# ProPrj_SunLight_2026-07-16.net
KiCad netlist of a schematic drawn in EasyEDA Pro
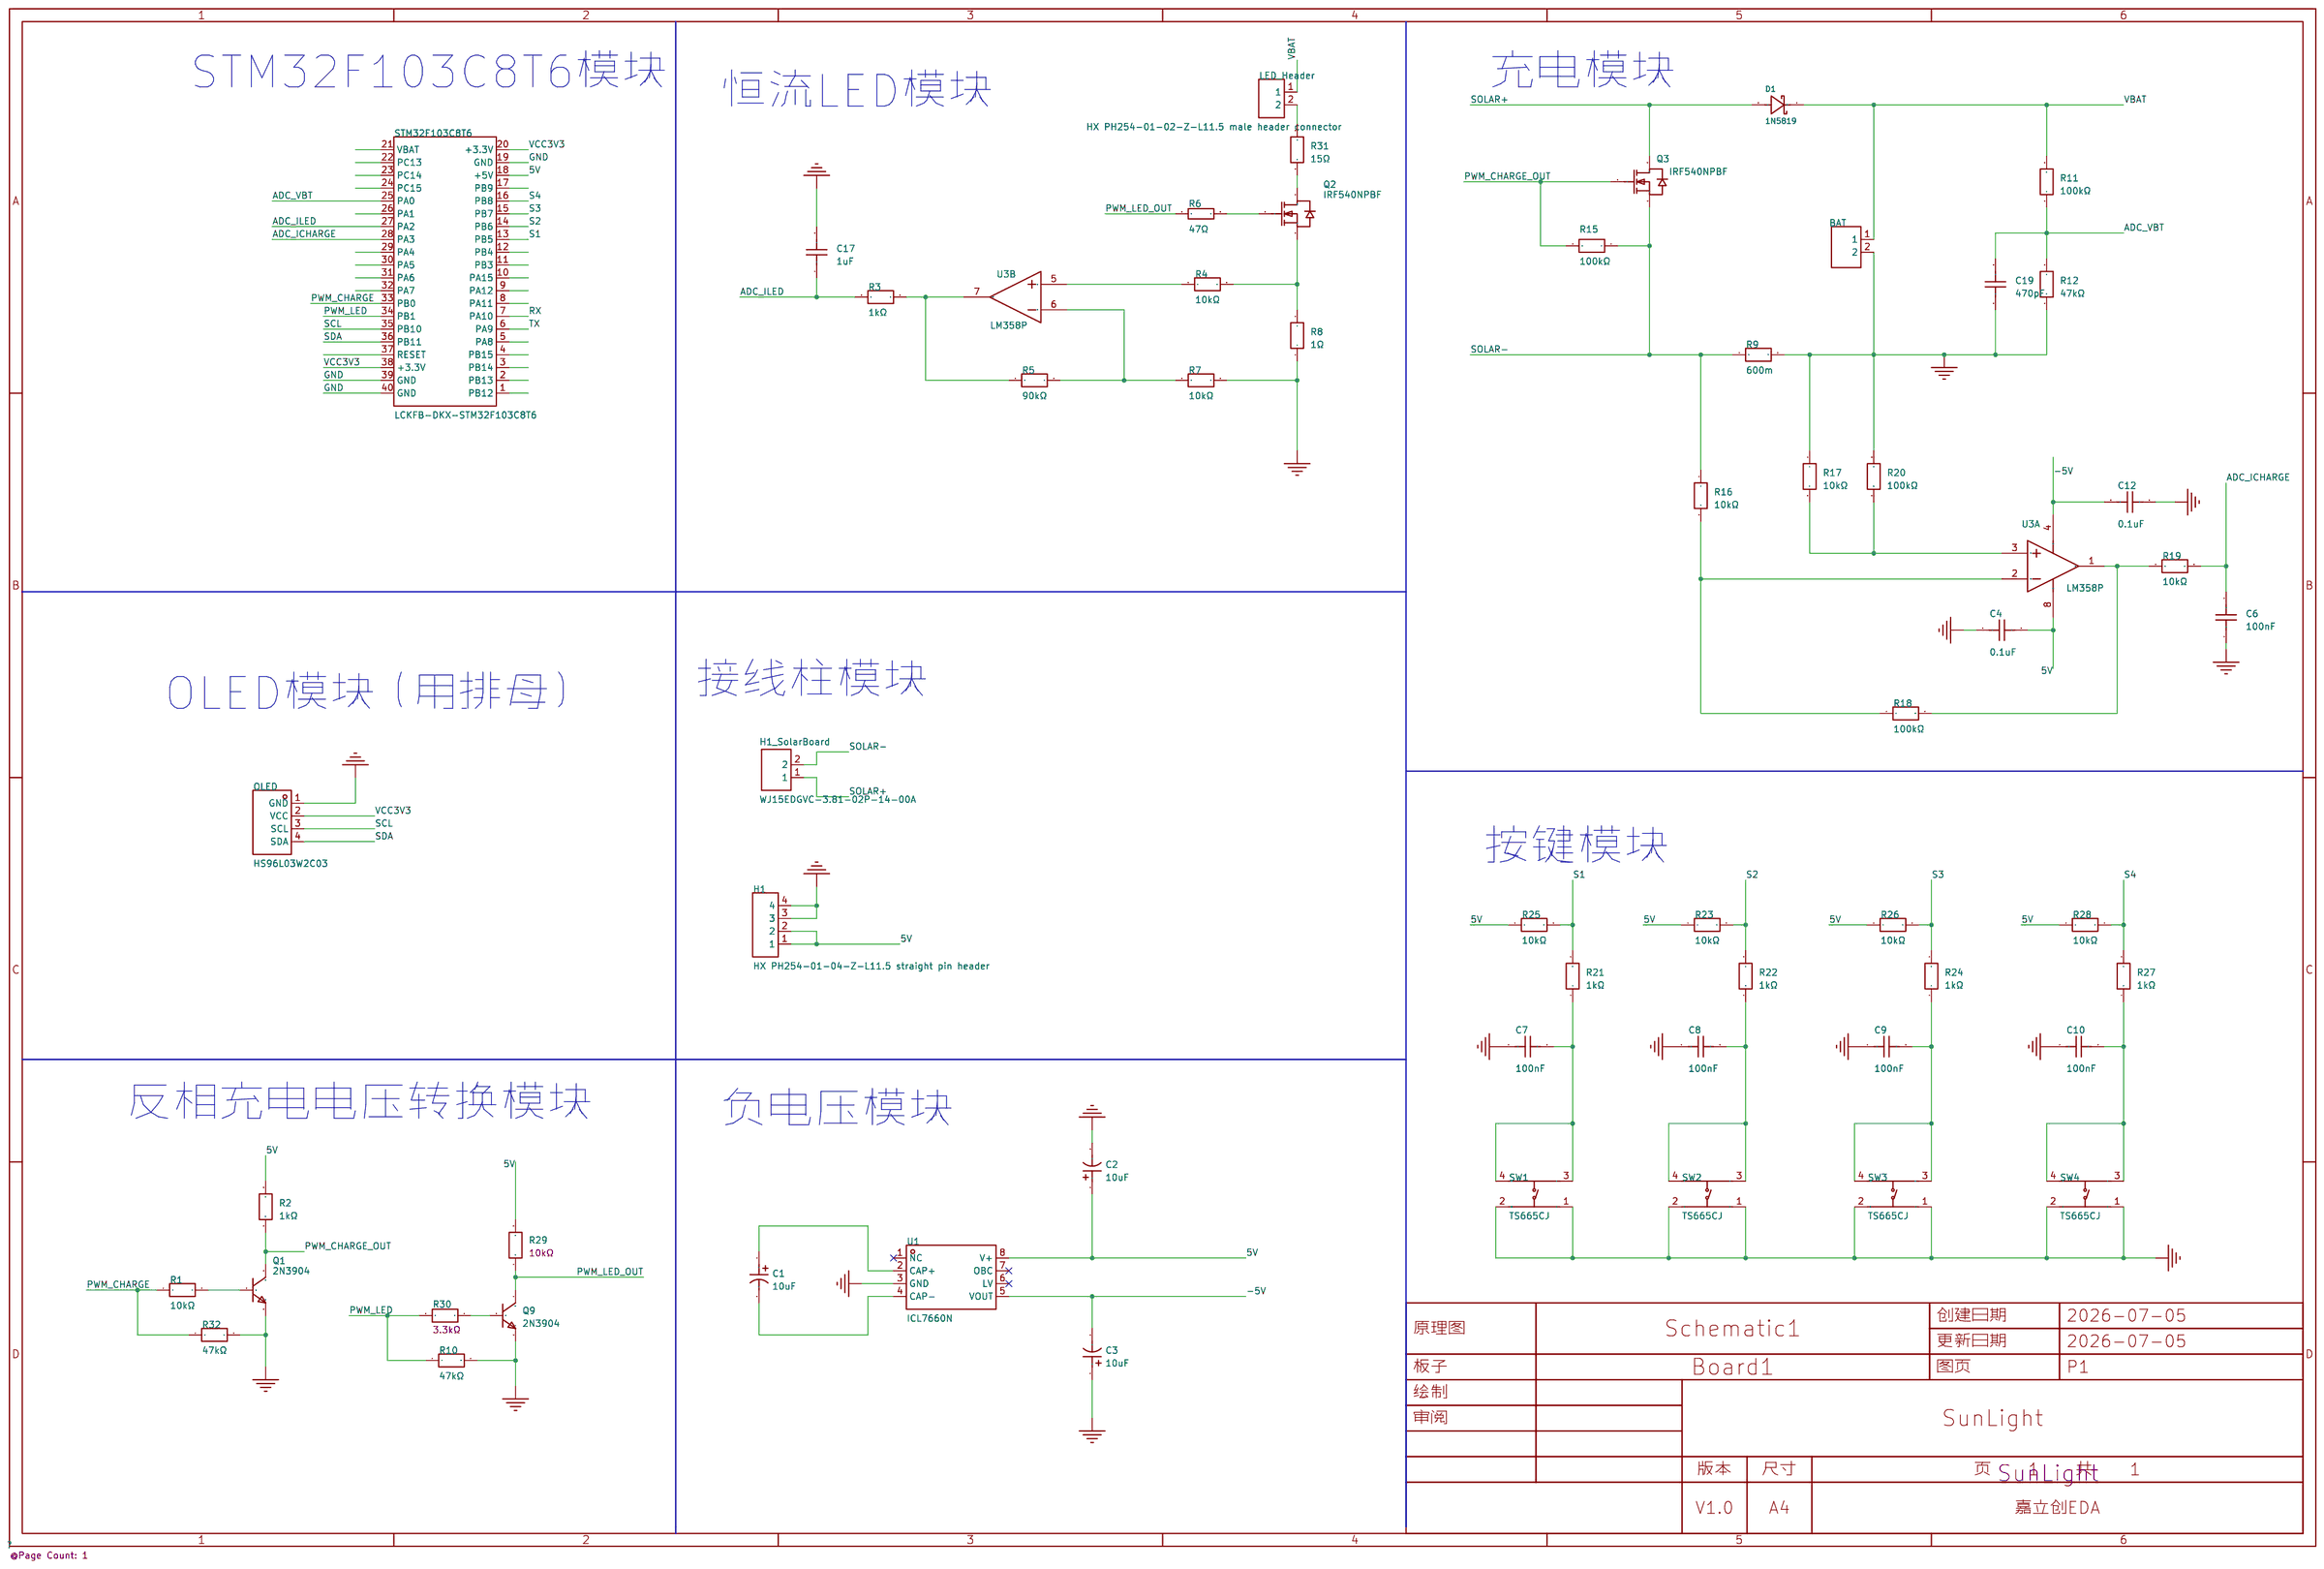
[diagram p0: schematic sheet]

(export (version "E")
  (design (tool "Eeschema 10.0.6"))
  (components
    (comp (ref "BAT")
      (value "WJ15EDGVC-3.81-02P-14-00A")
      (footprint "easyedapro:CONN-TH_WJ15EDGVC-3.81-2P")
      (fields (field (name "Manufacturer") "KANGNEX(康奈克斯电气)"))
      (libsource (lib "easyedapro") (part "WJ15EDGVC-3.81-2P"))
    )
    (comp (ref "C1")
      (value "10uF")
      (footprint "easyedapro:CAP-TH_BD10.0-P5.00-D0.6-FD_1")
      (fields (field (name "Manufacturer Part") "ERG450V10M10x16") (field (name "Manufacturer") "JIERR(捷而瑞)"))
      (libsource (lib "easyedapro") (part "ERG450V10M10X16"))
    )
    (comp (ref "C2")
      (value "10uF")
      (footprint "easyedapro:CAP-TH_BD10.0-P5.00-D0.6-FD_1")
      (fields (field (name "Manufacturer Part") "ERG450V10M10x16") (field (name "Manufacturer") "JIERR(捷而瑞)"))
      (libsource (lib "easyedapro") (part "ERG450V10M10X16"))
    )
    (comp (ref "C3")
      (value "10uF")
      (footprint "easyedapro:CAP-TH_BD10.0-P5.00-D0.6-FD_1")
      (fields (field (name "Manufacturer Part") "ERG450V10M10x16") (field (name "Manufacturer") "JIERR(捷而瑞)"))
      (libsource (lib "easyedapro") (part "ERG450V10M10X16"))
    )
    (comp (ref "C4")
      (value "0.1uF")
      (footprint "easyedapro:CAP-TH_L5.3-W3.2-P2.54-D0.6-S2.65")
      (description "容值:100nF;精度:-20%~+80%;额定电压:50V;温度系数:Y5V;")
      (fields
        (field (name "Manufacturer Part") "CC1H104ZA1ED3F5O1100")
        (field (name "Manufacturer") "Dersonic(德尔创)")
      )
      (libsource (lib "easyedapro") (part "CC1H104ZA1ED3F5O1100"))
    )
    (comp (ref "C6")
      (value "100nF")
      (footprint "easyedapro:CAP-TH_L5.5-W4.0-P5.00-D0.5")
      (fields
        (field (name "Manufacturer Part") "Y5P102K2KV16CC0224")
        (field (name "Manufacturer") "KNSCHA(科尼盛)")
      )
      (libsource (lib "easyedapro") (part "Y5P102K2KV16CC0224"))
    )
    (comp (ref "C7")
      (value "100nF")
      (footprint "easyedapro:CAP-TH_L5.5-W4.0-P5.00-D0.5")
      (fields
        (field (name "Manufacturer Part") "Y5P102K2KV16CC0224")
        (field (name "Manufacturer") "KNSCHA(科尼盛)")
      )
      (libsource (lib "easyedapro") (part "Y5P102K2KV16CC0224"))
    )
    (comp (ref "C8")
      (value "100nF")
      (footprint "easyedapro:CAP-TH_L5.5-W4.0-P5.00-D0.5")
      (fields
        (field (name "Manufacturer Part") "Y5P102K2KV16CC0224")
        (field (name "Manufacturer") "KNSCHA(科尼盛)")
      )
      (libsource (lib "easyedapro") (part "Y5P102K2KV16CC0224"))
    )
    (comp (ref "C9")
      (value "100nF")
      (footprint "easyedapro:CAP-TH_L5.5-W4.0-P5.00-D0.5")
      (fields
        (field (name "Manufacturer Part") "Y5P102K2KV16CC0224")
        (field (name "Manufacturer") "KNSCHA(科尼盛)")
      )
      (libsource (lib "easyedapro") (part "Y5P102K2KV16CC0224"))
    )
    (comp (ref "C10")
      (value "100nF")
      (footprint "easyedapro:CAP-TH_L5.5-W4.0-P5.00-D0.5")
      (fields
        (field (name "Manufacturer Part") "Y5P102K2KV16CC0224")
        (field (name "Manufacturer") "KNSCHA(科尼盛)")
      )
      (libsource (lib "easyedapro") (part "Y5P102K2KV16CC0224"))
    )
    (comp (ref "C12")
      (value "0.1uF")
      (footprint "easyedapro:CAP-TH_L5.3-W3.2-P2.54-D0.6-S2.65")
      (description "容值:100nF;精度:-20%~+80%;额定电压:50V;温度系数:Y5V;")
      (fields
        (field (name "Manufacturer Part") "CC1H104ZA1ED3F5O1100")
        (field (name "Manufacturer") "Dersonic(德尔创)")
      )
      (libsource (lib "easyedapro") (part "CC1H104ZA1ED3F5O1100"))
    )
    (comp (ref "C17")
      (value "1uF")
      (footprint "easyedapro:CAP-TH_L5.8-W2.8")
      (fields
        (field (name "Manufacturer Part") "CC1H104MC1FD3F6C10SA")
        (field (name "Manufacturer") "Dersonic(德尔创)")
      )
      (libsource (lib "easyedapro") (part "CC1H104MC1FD3F6C10SA"))
    )
    (comp (ref "C19")
      (value "470pF")
      (footprint "easyedapro:CAP-TH_L5.5-W4.0-P5.00-D0.5")
      (fields
        (field (name "Manufacturer Part") "Y5P102K2KV16CC0224")
        (field (name "Manufacturer") "KNSCHA(科尼盛)")
      )
      (libsource (lib "easyedapro") (part "Y5P102K2KV16CC0224"))
    )
    (comp (ref "D1")
      (value "1N5819")
      (footprint "easyedapro:DO-41_BD2.4-L4.7-P8.70-D0.9-RD")
      (fields (field (name "Manufacturer") "R+O(宏嘉诚)"))
      (libsource (lib "easyedapro") (part "1N5819_C54795756"))
    )
    (comp (ref "H1")
      (value "HX PH254-01-04-Z-L11.5 straight pin header")
      (footprint "easyedapro:HDR-TH_4P-HX-PH254-01-04-Z-L11.5")
      (fields (field (name "Manufacturer") "hanxia(韩下)"))
      (libsource (lib "easyedapro") (part "HX PH254-01-04-Z-L11.5 STRAIGHT PIN HEADER"))
    )
    (comp (ref "H1_SolarBoard")
      (value "WJ15EDGVC-3.81-02P-14-00A")
      (footprint "easyedapro:CONN-TH_WJ15EDGVC-3.81-2P")
      (fields (field (name "Manufacturer") "KANGNEX(康奈克斯电气)"))
      (libsource (lib "easyedapro") (part "WJ15EDGVC-3.81-2P"))
    )
    (comp (ref "LED_Header")
      (value "HX PH254-01-02-Z-L11.5 male header connector")
      (footprint "easyedapro:HDR-TH_2P-P2.54-V-M")
      (fields (field (name "Manufacturer") "hanxia(韩下)"))
      (libsource (lib "easyedapro") (part "HX PH254-01-02-Z-L11.5 MALE HEADER CONNECTOR"))
    )
    (comp (ref "OLED")
      (value "HS96L03W2C03")
      (footprint "easyedapro:OLED-TH_L27.8-W27.2-P2.54_C9900033791")
      (description "核心芯片:SSD1315芯片;接口类型:I2C;尺寸(inch):0.96;像素分辨率:128x64;")
      (fields (field (name "Manufacturer") "HS(汉昇)"))
      (libsource (lib "easyedapro") (part "HS96L03W2C03"))
    )
    (comp (ref "Q1")
      (value "2N3904")
      (footprint "easyedapro:TO-92-3_L4.6-W3.6-P1.27-L_1")
      (fields (field (name "Manufacturer") "JSMSEMI(杰盛微)"))
      (libsource (lib "easyedapro") (part "2N3904_C2874602"))
    )
    (comp (ref "Q2")
      (value "IRF540NPBF")
      (footprint "easyedapro:TO-220-3_L10.0-W4.5-P2.54-L")
      (fields (field (name "Manufacturer") "Infineon(英飞凌)"))
      (libsource (lib "easyedapro") (part "IRF540NPBF"))
    )
    (comp (ref "Q3")
      (value "IRF540NPBF")
      (footprint "easyedapro:TO-220-3_L10.0-W4.5-P2.54-L")
      (fields (field (name "Manufacturer") "Infineon(英飞凌)"))
      (libsource (lib "easyedapro") (part "IRF540NPBF"))
    )
    (comp (ref "Q9")
      (value "2N3904")
      (footprint "easyedapro:TO-92-3_L4.6-W3.6-P1.27-L_1")
      (description "晶体管类型:NPN;集电极电流(Ic):200mA;集射极击穿电压(Vceo):40V;耗散功率(Pd):625mW;直流电流增益(hFE):-;")
      (fields (field (name "Manufacturer") "JSMSEMI(杰盛微)"))
      (libsource (lib "easyedapro") (part "2N3904_C2874602"))
    )
    (comp (ref "R1")
      (value "10kΩ")
      (footprint "easyedapro:RES-TH_BD2.7-L6.2-P10.20-D0.4")
      (description "电阻类型:金属膜电阻;阻值:1kΩ;精度:±1%;功率:250mW;温度系数:±100ppm/℃;")
      (fields (field (name "Manufacturer Part") "MF1/4W-1K±1%-ST52") (field (name "Manufacturer") "VO(翔胜)"))
      (libsource (lib "easyedapro") (part "MF1/4W-1K±1%-ST52"))
    )
    (comp (ref "R2")
      (value "1kΩ")
      (footprint "easyedapro:RES-TH_BD2.7-L6.2-P10.20-D0.4")
      (description "电阻类型:金属膜电阻;阻值:1kΩ;精度:±1%;功率:250mW;温度系数:±100ppm/℃;")
      (fields (field (name "Manufacturer Part") "MF1/4W-1K±1%-ST52") (field (name "Manufacturer") "VO(翔胜)"))
      (libsource (lib "easyedapro") (part "MF1/4W-1K±1%-ST52"))
    )
    (comp (ref "R3")
      (value "1kΩ")
      (footprint "easyedapro:RES-TH_BD2.7-L6.2-P10.20-D0.4")
      (description "电阻类型:金属膜电阻;阻值:1kΩ;精度:±1%;功率:250mW;温度系数:±100ppm/℃;")
      (fields (field (name "Manufacturer Part") "MF1/4W-1K±1%-ST52") (field (name "Manufacturer") "VO(翔胜)"))
      (libsource (lib "easyedapro") (part "MF1/4W-1K±1%-ST52"))
    )
    (comp (ref "R4")
      (value "10kΩ")
      (footprint "easyedapro:RES-TH_BD2.7-L6.2-P10.20-D0.4")
      (description "电阻类型:金属膜电阻;阻值:1kΩ;精度:±1%;功率:250mW;温度系数:±100ppm/℃;")
      (fields (field (name "Manufacturer Part") "MF1/4W-1K±1%-ST52") (field (name "Manufacturer") "VO(翔胜)"))
      (libsource (lib "easyedapro") (part "MF1/4W-1K±1%-ST52"))
    )
    (comp (ref "R5")
      (value "90kΩ")
      (footprint "easyedapro:RES-TH_BD2.7-L6.2-P10.20-D0.4")
      (description "电阻类型:金属膜电阻;阻值:1kΩ;精度:±1%;功率:250mW;温度系数:±100ppm/℃;")
      (fields (field (name "Manufacturer Part") "MF1/4W-1K±1%-ST52") (field (name "Manufacturer") "VO(翔胜)"))
      (libsource (lib "easyedapro") (part "MF1/4W-1K±1%-ST52"))
    )
    (comp (ref "R6")
      (value "47Ω")
      (footprint "easyedapro:RES-TH_BD2.4-L6.3-P10.30-D0.6")
      (fields (field (name "Manufacturer Part") "MFR-25FTE52-47R") (field (name "Manufacturer") "YAGEO(国巨)"))
      (libsource (lib "easyedapro") (part "MFR-25FTE52-47R"))
    )
    (comp (ref "R7")
      (value "10kΩ")
      (footprint "easyedapro:RES-TH_BD2.7-L6.2-P10.20-D0.4")
      (description "电阻类型:金属膜电阻;阻值:1kΩ;精度:±1%;功率:250mW;温度系数:±100ppm/℃;")
      (fields (field (name "Manufacturer Part") "MF1/4W-1K±1%-ST52") (field (name "Manufacturer") "VO(翔胜)"))
      (libsource (lib "easyedapro") (part "MF1/4W-1K±1%-ST52"))
    )
    (comp (ref "R8")
      (value "1Ω")
      (footprint "easyedapro:RES-TH_BD2.7-L6.2-P10.20-D0.4")
      (description "电阻类型:金属膜电阻;阻值:1kΩ;精度:±1%;功率:250mW;温度系数:±100ppm/℃;")
      (fields (field (name "Manufacturer Part") "MF1/4W-1K±1%-ST52") (field (name "Manufacturer") "VO(翔胜)"))
      (libsource (lib "easyedapro") (part "MF1/4W-1K±1%-ST52"))
    )
    (comp (ref "R9")
      (value "600m")
      (footprint "easyedapro:RES-TH_BD2.7-L6.2-P10.20-D0.4")
      (description "电阻类型:金属膜电阻;阻值:1kΩ;精度:±1%;功率:250mW;温度系数:±100ppm/℃;")
      (fields (field (name "Manufacturer Part") "MF1/4W-1K±1%-ST52") (field (name "Manufacturer") "VO(翔胜)"))
      (libsource (lib "easyedapro") (part "MF1/4W-1K±1%-ST52"))
    )
    (comp (ref "R10")
      (value "47kΩ")
      (footprint "easyedapro:RES-TH_BD2.7-L6.2-P10.20-D0.4")
      (fields (field (name "Manufacturer Part") "MF1/4W-47K±1%-ST52") (field (name "Manufacturer") "VO(翔胜)"))
      (libsource (lib "easyedapro") (part "MF1/4W-47K±1%-ST52"))
    )
    (comp (ref "R11")
      (value "100kΩ")
      (footprint "easyedapro:RES-TH_BD2.7-L6.2-P10.20-D0.4")
      (description "电阻类型:金属膜电阻;阻值:1kΩ;精度:±1%;功率:250mW;温度系数:±100ppm/℃;")
      (fields (field (name "Manufacturer Part") "MF1/4W-1K±1%-ST52") (field (name "Manufacturer") "VO(翔胜)"))
      (libsource (lib "easyedapro") (part "MF1/4W-1K±1%-ST52"))
    )
    (comp (ref "R12")
      (value "47kΩ")
      (footprint "easyedapro:RES-TH_BD2.7-L6.2-P10.20-D0.4")
      (description "电阻类型:金属膜电阻;阻值:1kΩ;精度:±1%;功率:250mW;温度系数:±100ppm/℃;")
      (fields (field (name "Manufacturer Part") "MF1/4W-1K±1%-ST52") (field (name "Manufacturer") "VO(翔胜)"))
      (libsource (lib "easyedapro") (part "MF1/4W-1K±1%-ST52"))
    )
    (comp (ref "R15")
      (value "100kΩ")
      (footprint "easyedapro:RES-TH_BD2.7-L6.2-P10.20-D0.4")
      (description "电阻类型:金属膜电阻;阻值:1kΩ;精度:±1%;功率:250mW;温度系数:±100ppm/℃;")
      (fields (field (name "Manufacturer Part") "MF1/4W-1K±1%-ST52") (field (name "Manufacturer") "VO(翔胜)"))
      (libsource (lib "easyedapro") (part "MF1/4W-1K±1%-ST52"))
    )
    (comp (ref "R16")
      (value "10kΩ")
      (footprint "easyedapro:RES-TH_BD2.7-L6.2-P10.20-D0.4")
      (description "电阻类型:金属膜电阻;阻值:1kΩ;精度:±1%;功率:250mW;温度系数:±100ppm/℃;")
      (fields (field (name "Manufacturer Part") "MF1/4W-1K±1%-ST52") (field (name "Manufacturer") "VO(翔胜)"))
      (libsource (lib "easyedapro") (part "MF1/4W-1K±1%-ST52"))
    )
    (comp (ref "R17")
      (value "10kΩ")
      (footprint "easyedapro:RES-TH_BD2.7-L6.2-P10.20-D0.4")
      (description "电阻类型:金属膜电阻;阻值:1kΩ;精度:±1%;功率:250mW;温度系数:±100ppm/℃;")
      (fields (field (name "Manufacturer Part") "MF1/4W-1K±1%-ST52") (field (name "Manufacturer") "VO(翔胜)"))
      (libsource (lib "easyedapro") (part "MF1/4W-1K±1%-ST52"))
    )
    (comp (ref "R18")
      (value "100kΩ")
      (footprint "easyedapro:RES-TH_BD2.7-L6.2-P10.20-D0.4")
      (description "电阻类型:金属膜电阻;阻值:1kΩ;精度:±1%;功率:250mW;温度系数:±100ppm/℃;")
      (fields (field (name "Manufacturer Part") "MF1/4W-1K±1%-ST52") (field (name "Manufacturer") "VO(翔胜)"))
      (libsource (lib "easyedapro") (part "MF1/4W-1K±1%-ST52"))
    )
    (comp (ref "R19")
      (value "10kΩ")
      (footprint "easyedapro:RES-TH_BD2.7-L6.2-P10.20-D0.4")
      (description "电阻类型:金属膜电阻;阻值:1kΩ;精度:±1%;功率:250mW;温度系数:±100ppm/℃;")
      (fields (field (name "Manufacturer Part") "MF1/4W-1K±1%-ST52") (field (name "Manufacturer") "VO(翔胜)"))
      (libsource (lib "easyedapro") (part "MF1/4W-1K±1%-ST52"))
    )
    (comp (ref "R20")
      (value "100kΩ")
      (footprint "easyedapro:RES-TH_BD2.7-L6.2-P10.20-D0.4")
      (description "电阻类型:金属膜电阻;阻值:1kΩ;精度:±1%;功率:250mW;温度系数:±100ppm/℃;")
      (fields (field (name "Manufacturer Part") "MF1/4W-1K±1%-ST52") (field (name "Manufacturer") "VO(翔胜)"))
      (libsource (lib "easyedapro") (part "MF1/4W-1K±1%-ST52"))
    )
    (comp (ref "R21")
      (value "1kΩ")
      (footprint "easyedapro:RES-TH_BD2.7-L6.2-P10.20-D0.4")
      (description "电阻类型:金属膜电阻;阻值:1kΩ;精度:±1%;功率:250mW;温度系数:±100ppm/℃;")
      (fields (field (name "Manufacturer Part") "MF1/4W-1K±1%-ST52") (field (name "Manufacturer") "VO(翔胜)"))
      (libsource (lib "easyedapro") (part "MF1/4W-1K±1%-ST52"))
    )
    (comp (ref "R22")
      (value "1kΩ")
      (footprint "easyedapro:RES-TH_BD2.7-L6.2-P10.20-D0.4")
      (description "电阻类型:金属膜电阻;阻值:1kΩ;精度:±1%;功率:250mW;温度系数:±100ppm/℃;")
      (fields (field (name "Manufacturer Part") "MF1/4W-1K±1%-ST52") (field (name "Manufacturer") "VO(翔胜)"))
      (libsource (lib "easyedapro") (part "MF1/4W-1K±1%-ST52"))
    )
    (comp (ref "R23")
      (value "10kΩ")
      (footprint "easyedapro:RES-TH_BD2.7-L6.2-P10.20-D0.4")
      (description "电阻类型:金属膜电阻;阻值:1kΩ;精度:±1%;功率:250mW;温度系数:±100ppm/℃;")
      (fields (field (name "Manufacturer Part") "MF1/4W-1K±1%-ST52") (field (name "Manufacturer") "VO(翔胜)"))
      (libsource (lib "easyedapro") (part "MF1/4W-1K±1%-ST52"))
    )
    (comp (ref "R24")
      (value "1kΩ")
      (footprint "easyedapro:RES-TH_BD2.7-L6.2-P10.20-D0.4")
      (description "电阻类型:金属膜电阻;阻值:1kΩ;精度:±1%;功率:250mW;温度系数:±100ppm/℃;")
      (fields (field (name "Manufacturer Part") "MF1/4W-1K±1%-ST52") (field (name "Manufacturer") "VO(翔胜)"))
      (libsource (lib "easyedapro") (part "MF1/4W-1K±1%-ST52"))
    )
    (comp (ref "R25")
      (value "10kΩ")
      (footprint "easyedapro:RES-TH_BD2.7-L6.2-P10.20-D0.4")
      (description "电阻类型:金属膜电阻;阻值:1kΩ;精度:±1%;功率:250mW;温度系数:±100ppm/℃;")
      (fields (field (name "Manufacturer Part") "MF1/4W-1K±1%-ST52") (field (name "Manufacturer") "VO(翔胜)"))
      (libsource (lib "easyedapro") (part "MF1/4W-1K±1%-ST52"))
    )
    (comp (ref "R26")
      (value "10kΩ")
      (footprint "easyedapro:RES-TH_BD2.7-L6.2-P10.20-D0.4")
      (description "电阻类型:金属膜电阻;阻值:1kΩ;精度:±1%;功率:250mW;温度系数:±100ppm/℃;")
      (fields (field (name "Manufacturer Part") "MF1/4W-1K±1%-ST52") (field (name "Manufacturer") "VO(翔胜)"))
      (libsource (lib "easyedapro") (part "MF1/4W-1K±1%-ST52"))
    )
    (comp (ref "R27")
      (value "1kΩ")
      (footprint "easyedapro:RES-TH_BD2.7-L6.2-P10.20-D0.4")
      (description "电阻类型:金属膜电阻;阻值:1kΩ;精度:±1%;功率:250mW;温度系数:±100ppm/℃;")
      (fields (field (name "Manufacturer Part") "MF1/4W-1K±1%-ST52") (field (name "Manufacturer") "VO(翔胜)"))
      (libsource (lib "easyedapro") (part "MF1/4W-1K±1%-ST52"))
    )
    (comp (ref "R28")
      (value "10kΩ")
      (footprint "easyedapro:RES-TH_BD2.7-L6.2-P10.20-D0.4")
      (description "电阻类型:金属膜电阻;阻值:1kΩ;精度:±1%;功率:250mW;温度系数:±100ppm/℃;")
      (fields (field (name "Manufacturer Part") "MF1/4W-1K±1%-ST52") (field (name "Manufacturer") "VO(翔胜)"))
      (libsource (lib "easyedapro") (part "MF1/4W-1K±1%-ST52"))
    )
    (comp (ref "R29")
      (value "1kΩ")
      (footprint "easyedapro:RES-TH_BD2.7-L6.2-P10.20-D0.4")
      (description "电阻类型:金属膜电阻;阻值:1kΩ;精度:±1%;功率:250mW;温度系数:±100ppm/℃;")
      (fields
        (field (name "Manufacturer Part") "MF1/4W-1K±1%-ST52")
        (field (name "Manufacturer") "VO(翔胜)")
        (field (name "Resistance") "10kΩ")
      )
      (libsource (lib "easyedapro") (part "MF1/4W-1K±1%-ST52"))
    )
    (comp (ref "R30")
      (value "1kΩ")
      (footprint "easyedapro:RES-TH_BD2.7-L6.2-P10.20-D0.4")
      (description "电阻类型:金属膜电阻;阻值:1kΩ;精度:±1%;功率:250mW;温度系数:±100ppm/℃;")
      (fields
        (field (name "Manufacturer Part") "MF1/4W-1K±1%-ST52")
        (field (name "Manufacturer") "VO(翔胜)")
        (field (name "Resistance") "3.3kΩ")
      )
      (libsource (lib "easyedapro") (part "MF1/4W-1K±1%-ST52"))
    )
    (comp (ref "R31")
      (value "15Ω")
      (footprint "easyedapro:RES-TH_BD2.7-L6.2-P10.20-D0.4")
      (fields (field (name "Manufacturer Part") "MF1/4W-4Ω7±1%-OT26") (field (name "Manufacturer") "VO(翔胜)"))
      (libsource (lib "easyedapro") (part "MF1/4W-4Ω7±1%-OT26"))
    )
    (comp (ref "R32")
      (value "47kΩ")
      (footprint "easyedapro:RES-TH_BD2.7-L6.2-P10.20-D0.4")
      (fields (field (name "Manufacturer Part") "MF1/4W-47K±1%-ST52") (field (name "Manufacturer") "VO(翔胜)"))
      (libsource (lib "easyedapro") (part "MF1/4W-47K±1%-ST52"))
    )
    (comp (ref "STM32F103C8T6")
      (value "LCKFB-DKX-STM32F103C8T6")
      (footprint "easyedapro:CONN-TH_L53.3-W22.9_STM32F103C8T6-CARD")
      (fields (field (name "Manufacturer") "立创开发板"))
      (libsource (lib "easyedapro") (part "LCKFB-DKX-STM32F103C8T6"))
    )
    (comp (ref "SW1")
      (value "TS665CJ")
      (footprint "easyedapro:SW-TH_4P-L6.0-W6.0-P4.50-LS6.5")
      (fields (field (name "Manufacturer") "SHOU HAN(首韩)"))
      (libsource (lib "easyedapro") (part "TS665CJ"))
    )
    (comp (ref "SW2")
      (value "TS665CJ")
      (footprint "easyedapro:SW-TH_4P-L6.0-W6.0-P4.50-LS6.5")
      (fields (field (name "Manufacturer") "SHOU HAN(首韩)"))
      (libsource (lib "easyedapro") (part "TS665CJ"))
    )
    (comp (ref "SW3")
      (value "TS665CJ")
      (footprint "easyedapro:SW-TH_4P-L6.0-W6.0-P4.50-LS6.5")
      (fields (field (name "Manufacturer") "SHOU HAN(首韩)"))
      (libsource (lib "easyedapro") (part "TS665CJ"))
    )
    (comp (ref "SW4")
      (value "TS665CJ")
      (footprint "easyedapro:SW-TH_4P-L6.0-W6.0-P4.50-LS6.5")
      (fields (field (name "Manufacturer") "SHOU HAN(首韩)"))
      (libsource (lib "easyedapro") (part "TS665CJ"))
    )
    (comp (ref "U1")
      (value "ICL7660N")
      (footprint "easyedapro:DIP-8_L9.4-W6.4-P2.54-LS9.1-BL")
      (fields (field (name "Manufacturer") "HGSEMI(华冠)"))
      (libsource (lib "easyedapro") (part "ICL7660N"))
    )
    (comp (ref "U3")
      (value "LM358P")
      (footprint "easyedapro:DIP-8_L9.7-W6.4-P2.54-LS7.6-BL")
      (description "放大器数:2;轨到轨:-;增益带宽积(GBW):1MHz;输入失调电压(Vos):2mV;压摆率(SR):-;输入偏置电流(Ib):45nA;")
      (fields (field (name "Manufacturer") "Slkor(萨科微)"))
      (libsource (lib "easyedapro") (part "LM358P_C5330384"))
    )
  )
  (nets
    (net (code "1") (name "/-5V") (class "Default")
      (node (ref "C12") (pin "2") (pinfunction "2_2") (pintype "unspecified"))
      (node (ref "C3") (pin "2") (pinfunction "2_2") (pintype "input"))
      (node (ref "U1") (pin "5") (pinfunction "VOUT_5") (pintype "unspecified"))
      (node (ref "U3") (pin "4") (pinfunction "GND_4") (pintype "unspecified"))
    )
    (net (code "2") (name "/5V") (class "Default")
      (node (ref "C2") (pin "1") (pinfunction "1_1") (pintype "input"))
      (node (ref "C4") (pin "2") (pinfunction "2_2") (pintype "unspecified"))
      (node (ref "H1") (pin "1") (pinfunction "1_1") (pintype "unspecified"))
      (node (ref "H1") (pin "2") (pinfunction "2_2") (pintype "unspecified"))
      (node (ref "R2") (pin "2") (pinfunction "2_2") (pintype "unspecified"))
      (node (ref "R23") (pin "1") (pinfunction "1_1") (pintype "unspecified"))
      (node (ref "R25") (pin "1") (pinfunction "1_1") (pintype "unspecified"))
      (node (ref "R26") (pin "1") (pinfunction "1_1") (pintype "unspecified"))
      (node (ref "R28") (pin "1") (pinfunction "1_1") (pintype "unspecified"))
      (node (ref "R29") (pin "2") (pinfunction "2_2") (pintype "unspecified"))
      (node (ref "STM32F103C8T6") (pin "18") (pinfunction "+5V_18") (pintype "unspecified"))
      (node (ref "U1") (pin "8") (pinfunction "V+_8") (pintype "unspecified"))
      (node (ref "U3") (pin "8") (pinfunction "VCC_8") (pintype "unspecified"))
    )
    (net (code "3") (name "/ADC_ICHARGE") (class "Default")
      (node (ref "C6") (pin "2") (pinfunction "2_2") (pintype "unspecified"))
      (node (ref "R19") (pin "2") (pinfunction "2_2") (pintype "unspecified"))
      (node (ref "STM32F103C8T6") (pin "28") (pinfunction "PA3_28") (pintype "unspecified"))
    )
    (net (code "4") (name "/ADC_ILED") (class "Default")
      (node (ref "C17") (pin "1") (pinfunction "1_1") (pintype "unspecified"))
      (node (ref "R3") (pin "1") (pinfunction "1_1") (pintype "unspecified"))
      (node (ref "STM32F103C8T6") (pin "27") (pinfunction "PA2_27") (pintype "unspecified"))
    )
    (net (code "5") (name "/ADC_VBT") (class "Default")
      (node (ref "C19") (pin "2") (pinfunction "2_2") (pintype "unspecified"))
      (node (ref "R11") (pin "1") (pinfunction "1_1") (pintype "unspecified"))
      (node (ref "R12") (pin "2") (pinfunction "2_2") (pintype "unspecified"))
      (node (ref "STM32F103C8T6") (pin "25") (pinfunction "PA0_25") (pintype "unspecified"))
    )
    (net (code "6") (name "/PWM_CHARGE") (class "Default")
      (node (ref "R1") (pin "1") (pinfunction "1_1") (pintype "unspecified"))
      (node (ref "R32") (pin "1") (pinfunction "1_1") (pintype "unspecified"))
      (node (ref "STM32F103C8T6") (pin "33") (pinfunction "PB0_33") (pintype "unspecified"))
    )
    (net (code "7") (name "/PWM_CHARGE_OUT") (class "Default")
      (node (ref "Q1") (pin "1") (pinfunction "C_1") (pintype "unspecified"))
      (node (ref "Q3") (pin "1") (pinfunction "G_1") (pintype "unspecified"))
      (node (ref "R15") (pin "2") (pinfunction "2_2") (pintype "unspecified"))
      (node (ref "R2") (pin "1") (pinfunction "1_1") (pintype "unspecified"))
    )
    (net (code "8") (name "/PWM_LED") (class "Default")
      (node (ref "R10") (pin "1") (pinfunction "1_1") (pintype "unspecified"))
      (node (ref "R30") (pin "2") (pinfunction "2_2") (pintype "unspecified"))
      (node (ref "STM32F103C8T6") (pin "34") (pinfunction "PB1_34") (pintype "unspecified"))
    )
    (net (code "9") (name "/PWM_LED_OUT") (class "Default")
      (node (ref "Q9") (pin "1") (pinfunction "C_1") (pintype "unspecified"))
      (node (ref "R29") (pin "1") (pinfunction "1_1") (pintype "unspecified"))
      (node (ref "R6") (pin "1") (pinfunction "1_1") (pintype "unspecified"))
    )
    (net (code "10") (name "/RX") (class "Default")
      (node (ref "STM32F103C8T6") (pin "7") (pinfunction "PA10_7") (pintype "unspecified"))
    )
    (net (code "11") (name "/S1") (class "Default")
      (node (ref "R21") (pin "2") (pinfunction "2_2") (pintype "unspecified"))
      (node (ref "R25") (pin "2") (pinfunction "2_2") (pintype "unspecified"))
      (node (ref "STM32F103C8T6") (pin "13") (pinfunction "PB5_13") (pintype "unspecified"))
    )
    (net (code "12") (name "/S2") (class "Default")
      (node (ref "R22") (pin "2") (pinfunction "2_2") (pintype "unspecified"))
      (node (ref "R23") (pin "2") (pinfunction "2_2") (pintype "unspecified"))
      (node (ref "STM32F103C8T6") (pin "14") (pinfunction "PB6_14") (pintype "unspecified"))
    )
    (net (code "13") (name "/S3") (class "Default")
      (node (ref "R24") (pin "2") (pinfunction "2_2") (pintype "unspecified"))
      (node (ref "R26") (pin "2") (pinfunction "2_2") (pintype "unspecified"))
      (node (ref "STM32F103C8T6") (pin "15") (pinfunction "PB7_15") (pintype "unspecified"))
    )
    (net (code "14") (name "/S4") (class "Default")
      (node (ref "R27") (pin "2") (pinfunction "2_2") (pintype "unspecified"))
      (node (ref "R28") (pin "2") (pinfunction "2_2") (pintype "unspecified"))
      (node (ref "STM32F103C8T6") (pin "16") (pinfunction "PB8_16") (pintype "unspecified"))
    )
    (net (code "15") (name "/SCL") (class "Default")
      (node (ref "OLED") (pin "3") (pinfunction "SCL_3") (pintype "unspecified"))
      (node (ref "STM32F103C8T6") (pin "35") (pinfunction "PB10_35") (pintype "unspecified"))
    )
    (net (code "16") (name "/SDA") (class "Default")
      (node (ref "OLED") (pin "4") (pinfunction "SDA_4") (pintype "unspecified"))
      (node (ref "STM32F103C8T6") (pin "36") (pinfunction "PB11_36") (pintype "unspecified"))
    )
    (net (code "17") (name "/SOLAR+") (class "Default")
      (node (ref "D1") (pin "2") (pinfunction "A_2") (pintype "unspecified"))
      (node (ref "H1_SolarBoard") (pin "1") (pinfunction "1_1") (pintype "unspecified"))
      (node (ref "Q3") (pin "2") (pinfunction "D_2") (pintype "unspecified"))
    )
    (net (code "18") (name "/SOLAR-") (class "Default")
      (node (ref "H1_SolarBoard") (pin "2") (pinfunction "2_2") (pintype "unspecified"))
      (node (ref "Q3") (pin "3") (pinfunction "S_3") (pintype "unspecified"))
      (node (ref "R15") (pin "1") (pinfunction "1_1") (pintype "unspecified"))
      (node (ref "R16") (pin "1") (pinfunction "1_1") (pintype "unspecified"))
      (node (ref "R9") (pin "1") (pinfunction "1_1") (pintype "unspecified"))
    )
    (net (code "19") (name "/TX") (class "Default")
      (node (ref "STM32F103C8T6") (pin "6") (pinfunction "PA9_6") (pintype "unspecified"))
    )
    (net (code "20") (name "/VBAT") (class "Default")
      (node (ref "BAT") (pin "1") (pinfunction "1_1") (pintype "unspecified"))
      (node (ref "D1") (pin "1") (pinfunction "C_1") (pintype "unspecified"))
      (node (ref "LED_Header") (pin "1") (pinfunction "1_1") (pintype "unspecified"))
      (node (ref "R11") (pin "2") (pinfunction "2_2") (pintype "unspecified"))
    )
    (net (code "21") (name "/VCC3V3") (class "Default")
      (node (ref "OLED") (pin "2") (pinfunction "VCC_2") (pintype "unspecified"))
      (node (ref "STM32F103C8T6") (pin "20") (pinfunction "+3.3V_20") (pintype "unspecified"))
      (node (ref "STM32F103C8T6") (pin "38") (pinfunction "+3.3V_38") (pintype "unspecified"))
    )
    (net (code "22") (name "GND") (class "Default")
      (node (ref "BAT") (pin "2") (pinfunction "2_2") (pintype "unspecified"))
      (node (ref "C10") (pin "1") (pinfunction "1_1") (pintype "unspecified"))
      (node (ref "C12") (pin "1") (pinfunction "1_1") (pintype "unspecified"))
      (node (ref "C17") (pin "2") (pinfunction "2_2") (pintype "unspecified"))
      (node (ref "C19") (pin "1") (pinfunction "1_1") (pintype "unspecified"))
      (node (ref "C2") (pin "2") (pinfunction "2_2") (pintype "input"))
      (node (ref "C3") (pin "1") (pinfunction "1_1") (pintype "input"))
      (node (ref "C4") (pin "1") (pinfunction "1_1") (pintype "unspecified"))
      (node (ref "C6") (pin "1") (pinfunction "1_1") (pintype "unspecified"))
      (node (ref "C7") (pin "1") (pinfunction "1_1") (pintype "unspecified"))
      (node (ref "C8") (pin "1") (pinfunction "1_1") (pintype "unspecified"))
      (node (ref "C9") (pin "1") (pinfunction "1_1") (pintype "unspecified"))
      (node (ref "H1") (pin "3") (pinfunction "3_3") (pintype "unspecified"))
      (node (ref "H1") (pin "4") (pinfunction "4_4") (pintype "unspecified"))
      (node (ref "OLED") (pin "1") (pinfunction "GND_1") (pintype "unspecified"))
      (node (ref "Q1") (pin "3") (pinfunction "E_3") (pintype "unspecified"))
      (node (ref "Q9") (pin "3") (pinfunction "E_3") (pintype "unspecified"))
      (node (ref "R10") (pin "2") (pinfunction "2_2") (pintype "unspecified"))
      (node (ref "R12") (pin "1") (pinfunction "1_1") (pintype "unspecified"))
      (node (ref "R17") (pin "1") (pinfunction "1_1") (pintype "unspecified"))
      (node (ref "R20") (pin "2") (pinfunction "2_2") (pintype "unspecified"))
      (node (ref "R32") (pin "2") (pinfunction "2_2") (pintype "unspecified"))
      (node (ref "R7") (pin "2") (pinfunction "2_2") (pintype "unspecified"))
      (node (ref "R8") (pin "1") (pinfunction "1_1") (pintype "unspecified"))
      (node (ref "R9") (pin "2") (pinfunction "2_2") (pintype "unspecified"))
      (node (ref "STM32F103C8T6") (pin "19") (pinfunction "GND_19") (pintype "unspecified"))
      (node (ref "STM32F103C8T6") (pin "39") (pinfunction "GND_39") (pintype "unspecified"))
      (node (ref "STM32F103C8T6") (pin "40") (pinfunction "GND_40") (pintype "unspecified"))
      (node (ref "SW1") (pin "1") (pinfunction "A_1") (pintype "unspecified"))
      (node (ref "SW1") (pin "2") (pinfunction "B_2") (pintype "unspecified"))
      (node (ref "SW2") (pin "1") (pinfunction "A_1") (pintype "unspecified"))
      (node (ref "SW2") (pin "2") (pinfunction "B_2") (pintype "unspecified"))
      (node (ref "SW3") (pin "1") (pinfunction "A_1") (pintype "unspecified"))
      (node (ref "SW3") (pin "2") (pinfunction "B_2") (pintype "unspecified"))
      (node (ref "SW4") (pin "1") (pinfunction "A_1") (pintype "unspecified"))
      (node (ref "SW4") (pin "2") (pinfunction "B_2") (pintype "unspecified"))
      (node (ref "U1") (pin "3") (pinfunction "GND_3") (pintype "unspecified"))
    )
    (net (code "23") (name "Net-(LED_Header-Pad2)") (class "Default")
      (node (ref "LED_Header") (pin "2") (pinfunction "2_2") (pintype "unspecified"))
      (node (ref "R31") (pin "2") (pinfunction "2_2") (pintype "unspecified"))
    )
    (net (code "24") (name "Net-(Q1-B)") (class "Default")
      (node (ref "Q1") (pin "2") (pinfunction "B_2") (pintype "unspecified"))
      (node (ref "R1") (pin "2") (pinfunction "2_2") (pintype "unspecified"))
    )
    (net (code "25") (name "Net-(Q2-D)") (class "Default")
      (node (ref "Q2") (pin "2") (pinfunction "D_2") (pintype "unspecified"))
      (node (ref "R31") (pin "1") (pinfunction "1_1") (pintype "unspecified"))
    )
    (net (code "26") (name "Net-(Q2-G)") (class "Default")
      (node (ref "Q2") (pin "1") (pinfunction "G_1") (pintype "unspecified"))
      (node (ref "R6") (pin "2") (pinfunction "2_2") (pintype "unspecified"))
    )
    (net (code "27") (name "Net-(Q2-S)") (class "Default")
      (node (ref "Q2") (pin "3") (pinfunction "S_3") (pintype "unspecified"))
      (node (ref "R4") (pin "2") (pinfunction "2_2") (pintype "unspecified"))
      (node (ref "R8") (pin "2") (pinfunction "2_2") (pintype "unspecified"))
    )
    (net (code "28") (name "Net-(Q9-B)") (class "Default")
      (node (ref "Q9") (pin "2") (pinfunction "B_2") (pintype "unspecified"))
      (node (ref "R30") (pin "1") (pinfunction "1_1") (pintype "unspecified"))
    )
    (net (code "29") (name "Net-(SW1-C)") (class "Default")
      (node (ref "C7") (pin "2") (pinfunction "2_2") (pintype "unspecified"))
      (node (ref "R21") (pin "1") (pinfunction "1_1") (pintype "unspecified"))
      (node (ref "SW1") (pin "3") (pinfunction "C_3") (pintype "unspecified"))
      (node (ref "SW1") (pin "4") (pinfunction "D_4") (pintype "unspecified"))
    )
    (net (code "30") (name "Net-(SW2-C)") (class "Default")
      (node (ref "C8") (pin "2") (pinfunction "2_2") (pintype "unspecified"))
      (node (ref "R22") (pin "1") (pinfunction "1_1") (pintype "unspecified"))
      (node (ref "SW2") (pin "3") (pinfunction "C_3") (pintype "unspecified"))
      (node (ref "SW2") (pin "4") (pinfunction "D_4") (pintype "unspecified"))
    )
    (net (code "31") (name "Net-(SW3-C)") (class "Default")
      (node (ref "C9") (pin "2") (pinfunction "2_2") (pintype "unspecified"))
      (node (ref "R24") (pin "1") (pinfunction "1_1") (pintype "unspecified"))
      (node (ref "SW3") (pin "3") (pinfunction "C_3") (pintype "unspecified"))
      (node (ref "SW3") (pin "4") (pinfunction "D_4") (pintype "unspecified"))
    )
    (net (code "32") (name "Net-(SW4-C)") (class "Default")
      (node (ref "C10") (pin "2") (pinfunction "2_2") (pintype "unspecified"))
      (node (ref "R27") (pin "1") (pinfunction "1_1") (pintype "unspecified"))
      (node (ref "SW4") (pin "3") (pinfunction "C_3") (pintype "unspecified"))
      (node (ref "SW4") (pin "4") (pinfunction "D_4") (pintype "unspecified"))
    )
    (net (code "33") (name "Net-(U1-CAP+)") (class "Default")
      (node (ref "C1") (pin "1") (pinfunction "1_1") (pintype "input"))
      (node (ref "U1") (pin "2") (pinfunction "CAP+_2") (pintype "unspecified"))
    )
    (net (code "34") (name "Net-(U1-CAP-)") (class "Default")
      (node (ref "C1") (pin "2") (pinfunction "2_2") (pintype "input"))
      (node (ref "U1") (pin "4") (pinfunction "CAP-_4") (pintype "unspecified"))
    )
    (net (code "35") (name "Net-(U3A-IN1+)") (class "Default")
      (node (ref "R17") (pin "2") (pinfunction "2_2") (pintype "unspecified"))
      (node (ref "R20") (pin "1") (pinfunction "1_1") (pintype "unspecified"))
      (node (ref "U3") (pin "3") (pinfunction "IN1+_3") (pintype "unspecified"))
    )
    (net (code "36") (name "Net-(U3A-IN1-)") (class "Default")
      (node (ref "R16") (pin "2") (pinfunction "2_2") (pintype "unspecified"))
      (node (ref "R18") (pin "1") (pinfunction "1_1") (pintype "unspecified"))
      (node (ref "U3") (pin "2") (pinfunction "IN1-_2") (pintype "unspecified"))
    )
    (net (code "37") (name "Net-(U3A-OUT1)") (class "Default")
      (node (ref "R18") (pin "2") (pinfunction "2_2") (pintype "unspecified"))
      (node (ref "R19") (pin "1") (pinfunction "1_1") (pintype "unspecified"))
      (node (ref "U3") (pin "1") (pinfunction "OUT1_1") (pintype "output"))
    )
    (net (code "38") (name "Net-(U3B-IN2+)") (class "Default")
      (node (ref "R4") (pin "1") (pinfunction "1_1") (pintype "unspecified"))
      (node (ref "U3") (pin "5") (pinfunction "IN2+_5") (pintype "unspecified"))
    )
    (net (code "39") (name "Net-(U3B-IN2-)") (class "Default")
      (node (ref "R5") (pin "2") (pinfunction "2_2") (pintype "unspecified"))
      (node (ref "R7") (pin "1") (pinfunction "1_1") (pintype "unspecified"))
      (node (ref "U3") (pin "6") (pinfunction "IN2-_6") (pintype "unspecified"))
    )
    (net (code "40") (name "Net-(U3B-OUT2)") (class "Default")
      (node (ref "R3") (pin "2") (pinfunction "2_2") (pintype "unspecified"))
      (node (ref "R5") (pin "1") (pinfunction "1_1") (pintype "unspecified"))
      (node (ref "U3") (pin "7") (pinfunction "OUT2_7") (pintype "output"))
    )
    (net (code "41") (name "unconnected-(STM32F103C8T6-PA1-Pad26)") (class "Default")
      (node (ref "STM32F103C8T6") (pin "26") (pinfunction "PA1_26") (pintype "unspecified"))
    )
    (net (code "42") (name "unconnected-(STM32F103C8T6-PA4-Pad29)") (class "Default")
      (node (ref "STM32F103C8T6") (pin "29") (pinfunction "PA4_29") (pintype "unspecified"))
    )
    (net (code "43") (name "unconnected-(STM32F103C8T6-PA5-Pad30)") (class "Default")
      (node (ref "STM32F103C8T6") (pin "30") (pinfunction "PA5_30") (pintype "unspecified"))
    )
    (net (code "44") (name "unconnected-(STM32F103C8T6-PA6-Pad31)") (class "Default")
      (node (ref "STM32F103C8T6") (pin "31") (pinfunction "PA6_31") (pintype "unspecified"))
    )
    (net (code "45") (name "unconnected-(STM32F103C8T6-PA7-Pad32)") (class "Default")
      (node (ref "STM32F103C8T6") (pin "32") (pinfunction "PA7_32") (pintype "unspecified"))
    )
    (net (code "46") (name "unconnected-(STM32F103C8T6-PA8-Pad5)") (class "Default")
      (node (ref "STM32F103C8T6") (pin "5") (pinfunction "PA8_5") (pintype "unspecified"))
    )
    (net (code "47") (name "unconnected-(STM32F103C8T6-PA11-Pad8)") (class "Default")
      (node (ref "STM32F103C8T6") (pin "8") (pinfunction "PA11_8") (pintype "unspecified"))
    )
    (net (code "48") (name "unconnected-(STM32F103C8T6-PA12-Pad9)") (class "Default")
      (node (ref "STM32F103C8T6") (pin "9") (pinfunction "PA12_9") (pintype "unspecified"))
    )
    (net (code "49") (name "unconnected-(STM32F103C8T6-PA15-Pad10)") (class "Default")
      (node (ref "STM32F103C8T6") (pin "10") (pinfunction "PA15_10") (pintype "unspecified"))
    )
    (net (code "50") (name "unconnected-(STM32F103C8T6-PB3-Pad11)") (class "Default")
      (node (ref "STM32F103C8T6") (pin "11") (pinfunction "PB3_11") (pintype "unspecified"))
    )
    (net (code "51") (name "unconnected-(STM32F103C8T6-PB4-Pad12)") (class "Default")
      (node (ref "STM32F103C8T6") (pin "12") (pinfunction "PB4_12") (pintype "unspecified"))
    )
    (net (code "52") (name "unconnected-(STM32F103C8T6-PB9-Pad17)") (class "Default")
      (node (ref "STM32F103C8T6") (pin "17") (pinfunction "PB9_17") (pintype "unspecified"))
    )
    (net (code "53") (name "unconnected-(STM32F103C8T6-PB12-Pad1)") (class "Default")
      (node (ref "STM32F103C8T6") (pin "1") (pinfunction "PB12_1") (pintype "unspecified"))
    )
    (net (code "54") (name "unconnected-(STM32F103C8T6-PB13-Pad2)") (class "Default")
      (node (ref "STM32F103C8T6") (pin "2") (pinfunction "PB13_2") (pintype "unspecified"))
    )
    (net (code "55") (name "unconnected-(STM32F103C8T6-PB14-Pad3)") (class "Default")
      (node (ref "STM32F103C8T6") (pin "3") (pinfunction "PB14_3") (pintype "unspecified"))
    )
    (net (code "56") (name "unconnected-(STM32F103C8T6-PB15-Pad4)") (class "Default")
      (node (ref "STM32F103C8T6") (pin "4") (pinfunction "PB15_4") (pintype "unspecified"))
    )
    (net (code "57") (name "unconnected-(STM32F103C8T6-PC13-Pad22)") (class "Default")
      (node (ref "STM32F103C8T6") (pin "22") (pinfunction "PC13_22") (pintype "unspecified"))
    )
    (net (code "58") (name "unconnected-(STM32F103C8T6-PC14-Pad23)") (class "Default")
      (node (ref "STM32F103C8T6") (pin "23") (pinfunction "PC14_23") (pintype "unspecified"))
    )
    (net (code "59") (name "unconnected-(STM32F103C8T6-PC15-Pad24)") (class "Default")
      (node (ref "STM32F103C8T6") (pin "24") (pinfunction "PC15_24") (pintype "unspecified"))
    )
    (net (code "60") (name "unconnected-(STM32F103C8T6-RESET-Pad37)") (class "Default")
      (node (ref "STM32F103C8T6") (pin "37") (pinfunction "RESET_37") (pintype "unspecified"))
    )
    (net (code "61") (name "unconnected-(STM32F103C8T6-VBAT-Pad21)") (class "Default")
      (node (ref "STM32F103C8T6") (pin "21") (pinfunction "VBAT_21") (pintype "unspecified"))
    )
    (net (code "62") (name "unconnected-(U1-LV-Pad6)") (class "Default")
      (node (ref "U1") (pin "6") (pinfunction "LV_6") (pintype "unspecified+no_connect"))
    )
    (net (code "63") (name "unconnected-(U1-NC-Pad1)") (class "Default")
      (node (ref "U1") (pin "1") (pinfunction "NC_1") (pintype "unspecified+no_connect"))
    )
    (net (code "64") (name "unconnected-(U1-OBC-Pad7)") (class "Default")
      (node (ref "U1") (pin "7") (pinfunction "OBC_7") (pintype "unspecified+no_connect"))
    )
  )
)
